# MCU.net
KiCad netlist of a schematic drawn in Altium Designer
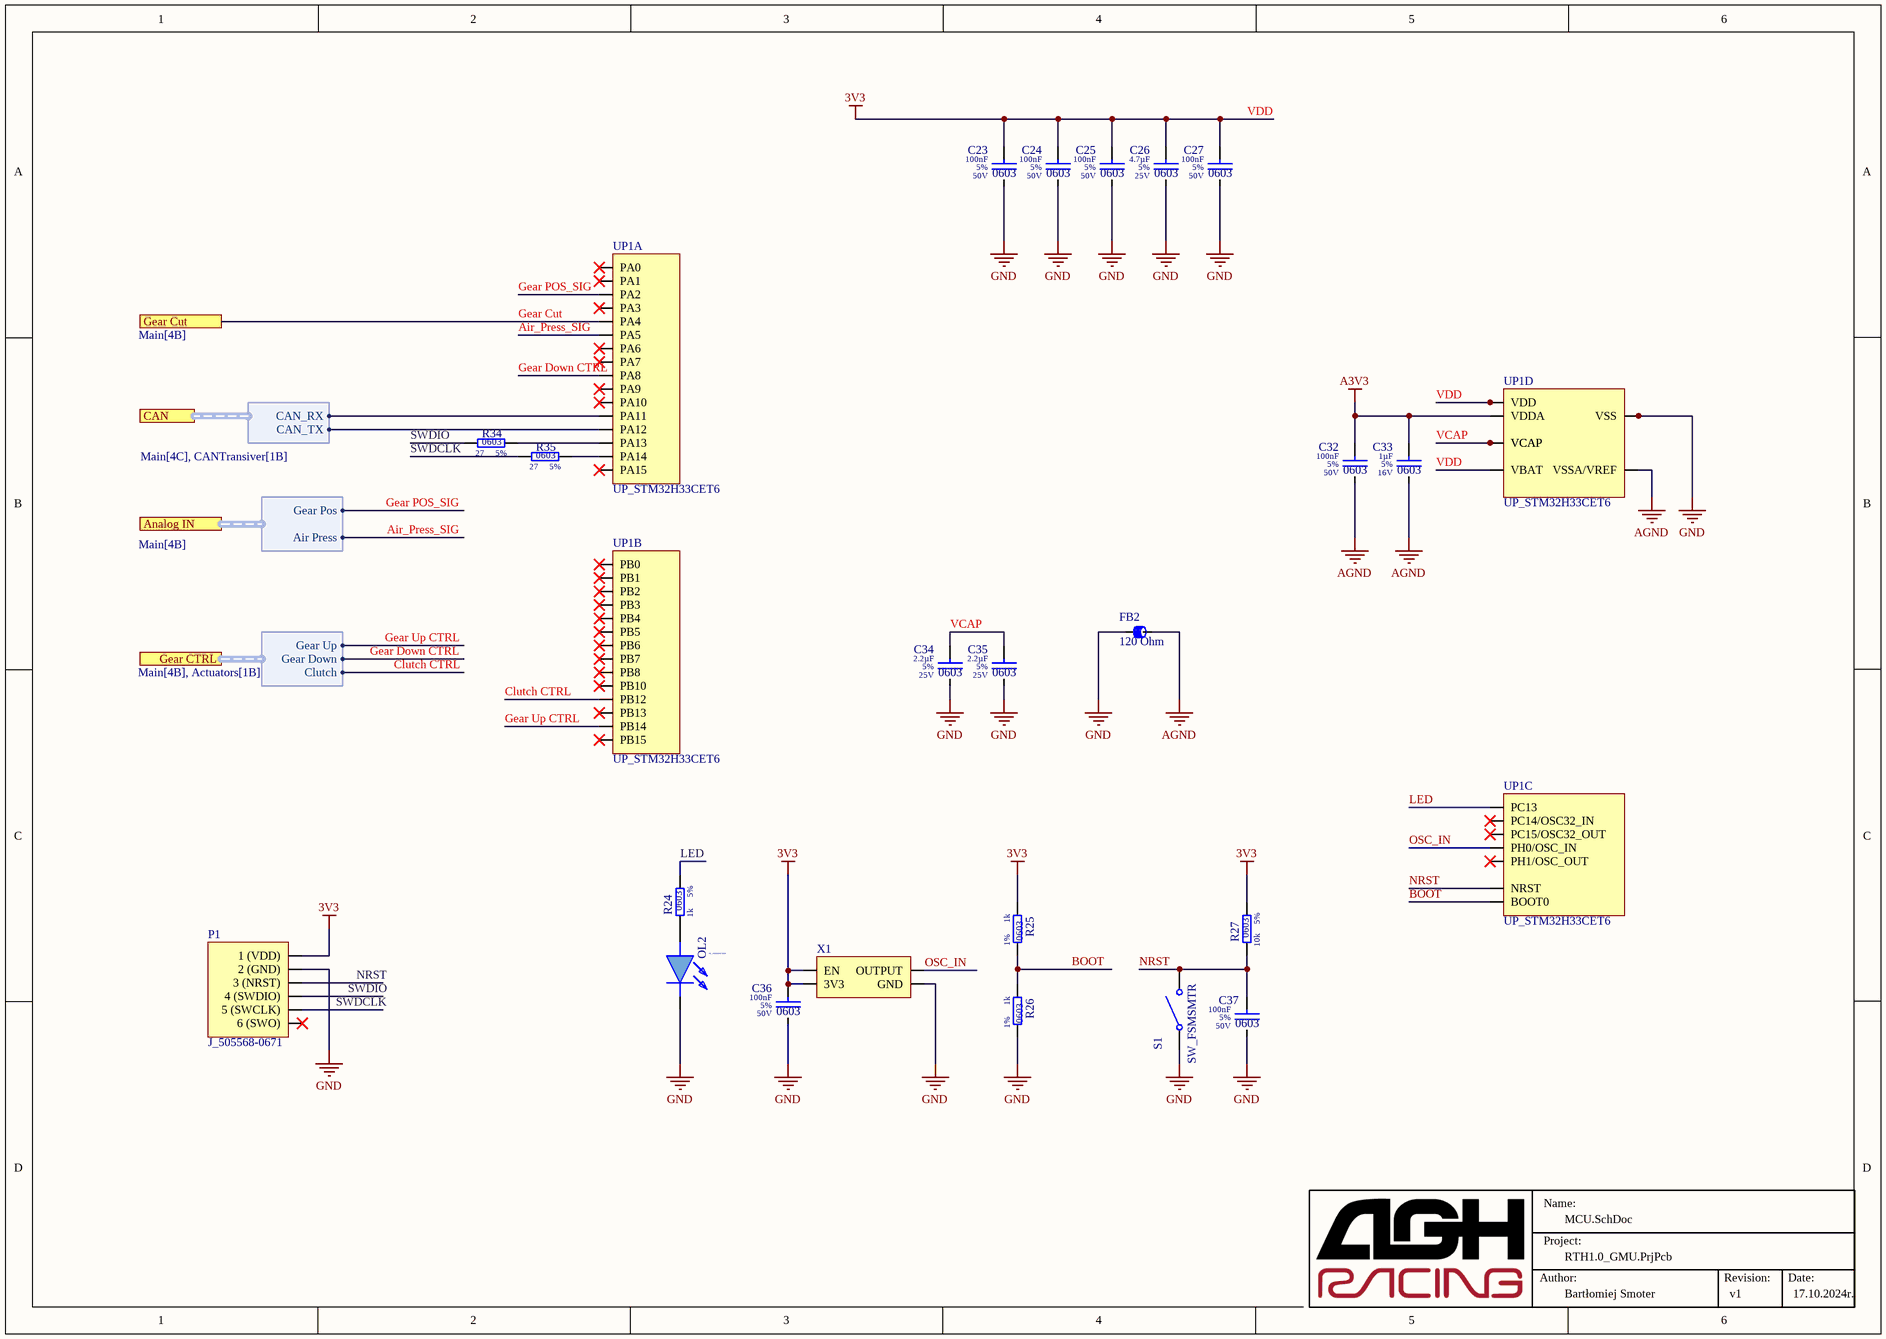
[diagram p0: MCU.SchDoc]

(export (version "E")
  (design (tool "Eeschema 10.0.6"))
  (components
    (comp (ref "C23")
      (value "100nF")
      (footprint "0603_HandSold_Capacitor")
      (description "C_100n_50V_0603_5")
      (fields
        (field (name "TOLERANCE") "5%")
        (field (name "VOLTAGE RATING") "50V")
        (field (name "CASE/PACKAGE") "0603")
      )
      (libsource (lib "Altium Concord Pro on A365") (part "Capacitor"))
    )
    (comp (ref "C24")
      (value "100nF")
      (footprint "0603_HandSold_Capacitor")
      (description "C_100n_50V_0603_5")
      (fields
        (field (name "TOLERANCE") "5%")
        (field (name "VOLTAGE RATING") "50V")
        (field (name "CASE/PACKAGE") "0603")
      )
      (libsource (lib "Altium Concord Pro on A365") (part "Capacitor"))
    )
    (comp (ref "C25")
      (value "100nF")
      (footprint "0603_HandSold_Capacitor")
      (description "C_100n_50V_0603_5")
      (fields
        (field (name "TOLERANCE") "5%")
        (field (name "VOLTAGE RATING") "50V")
        (field (name "CASE/PACKAGE") "0603")
      )
      (libsource (lib "Altium Concord Pro on A365") (part "Capacitor"))
    )
    (comp (ref "C26")
      (value "4.7µF")
      (footprint "0603_HandSold_Capacitor")
      (description "C_4.7u_25V_0603_5")
      (fields
        (field (name "TOLERANCE") "5%")
        (field (name "VOLTAGE RATING") "25V")
        (field (name "CASE/PACKAGE") "0603")
      )
      (libsource (lib "Altium Concord Pro on A365") (part "Capacitor"))
    )
    (comp (ref "C27")
      (value "100nF")
      (footprint "0603_HandSold_Capacitor")
      (description "C_100n_50V_0603_5")
      (fields
        (field (name "TOLERANCE") "5%")
        (field (name "VOLTAGE RATING") "50V")
        (field (name "CASE/PACKAGE") "0603")
      )
      (libsource (lib "Altium Concord Pro on A365") (part "Capacitor"))
    )
    (comp (ref "C32")
      (value "100nF")
      (footprint "0603_HandSold_Capacitor")
      (description "C_100n_50V_0603_5")
      (fields
        (field (name "TOLERANCE") "5%")
        (field (name "VOLTAGE RATING") "50V")
        (field (name "CASE/PACKAGE") "0603")
      )
      (libsource (lib "Altium Concord Pro on A365") (part "Capacitor"))
    )
    (comp (ref "C33")
      (value "1µF")
      (footprint "0603_HandSold_Capacitor")
      (description "C_1u_16V_0603_5")
      (fields
        (field (name "TOLERANCE") "5%")
        (field (name "VOLTAGE RATING") "16V")
        (field (name "CASE/PACKAGE") "0603")
      )
      (libsource (lib "Altium Concord Pro on A365") (part "Capacitor"))
    )
    (comp (ref "C34")
      (value "2.2µF")
      (footprint "0603_HandSold_Capacitor")
      (description "C_2.2u_25V_0603_5")
      (fields
        (field (name "TOLERANCE") "5%")
        (field (name "VOLTAGE RATING") "25V")
        (field (name "CASE/PACKAGE") "0603")
      )
      (libsource (lib "Altium Concord Pro on A365") (part "Capacitor"))
    )
    (comp (ref "C35")
      (value "2.2µF")
      (footprint "0603_HandSold_Capacitor")
      (description "C_2.2u_25V_0603_5")
      (fields
        (field (name "TOLERANCE") "5%")
        (field (name "VOLTAGE RATING") "25V")
        (field (name "CASE/PACKAGE") "0603")
      )
      (libsource (lib "Altium Concord Pro on A365") (part "Capacitor"))
    )
    (comp (ref "C36")
      (value "100nF")
      (footprint "0603_HandSold_Capacitor")
      (description "C_100n_50V_0603_5")
      (fields
        (field (name "TOLERANCE") "5%")
        (field (name "VOLTAGE RATING") "50V")
        (field (name "CASE/PACKAGE") "0603")
      )
      (libsource (lib "Altium Concord Pro on A365") (part "Capacitor"))
    )
    (comp (ref "C37")
      (value "100nF")
      (footprint "0603_HandSold_Capacitor")
      (description "C_100n_50V_0603_5")
      (fields
        (field (name "TOLERANCE") "5%")
        (field (name "VOLTAGE RATING") "50V")
        (field (name "CASE/PACKAGE") "0603")
      )
      (libsource (lib "Altium Concord Pro on A365") (part "Capacitor"))
    )
    (comp (ref "FB2")
      (value "FB_BLM21PG121SN1D")
      (footprint "0805_FB")
      (description "Ferrite Beads 120 OHM 25% Alternate Sizing Guide Below")
      (fields (field (name "IMPEDANCE") "120 Ohm"))
      (libsource (lib "Altium Concord Pro on A365") (part "FerriteBead"))
    )
    (comp (ref "OL2")
      (value "OL_150060BS75000")
      (footprint "0603_HandSold_LED")
      (description "LED 0603, Blue, 3.2V, 30mA, 105mW")
      (fields (field (name "POWER") "105mW"))
      (libsource (lib "Altium Concord Pro on A365") (part "OL_BLUE"))
    )
    (comp (ref "P1")
      (value "J_505568-0671")
      (footprint "505568-0671")
      (description "Male; Micro-Lock Plus; 6 Pos. 1.25mm; 1.5A 50V; Straight; SMT;")
      (libsource (lib "Altium Concord Pro on A365") (part "505568-0671"))
    )
    (comp (ref "R24")
      (value "R_1k_0603_5")
      (footprint "0603_HandSold_Resistor")
      (fields
        (field (name "TOLERANCE") "5%")
        (field (name "RESISTANCE") "1k")
        (field (name "CASE/PACKAGE") "0603")
        (field (name "POWER") "100mW")
      )
      (libsource (lib "Altium Concord Pro on A365") (part "Resistor"))
    )
    (comp (ref "R25")
      (value "R_1k_0603_1")
      (footprint "0603_HandSold_Resistor")
      (fields
        (field (name "TOLERANCE") "1%")
        (field (name "RESISTANCE") "1k")
        (field (name "CASE/PACKAGE") "0603")
        (field (name "POWER") "100mW")
      )
      (libsource (lib "Altium Concord Pro on A365") (part "Resistor"))
    )
    (comp (ref "R26")
      (value "R_1k_0603_1")
      (footprint "0603_HandSold_Resistor")
      (fields
        (field (name "TOLERANCE") "1%")
        (field (name "RESISTANCE") "1k")
        (field (name "CASE/PACKAGE") "0603")
        (field (name "POWER") "100mW")
      )
      (libsource (lib "Altium Concord Pro on A365") (part "Resistor"))
    )
    (comp (ref "R27")
      (value "R_10k_0603_5")
      (footprint "0603_HandSold_Resistor")
      (fields
        (field (name "TOLERANCE") "5%")
        (field (name "RESISTANCE") "10k")
        (field (name "CASE/PACKAGE") "0603")
        (field (name "POWER") "100mW")
      )
      (libsource (lib "Altium Concord Pro on A365") (part "Resistor"))
    )
    (comp (ref "R34")
      (value "R_27_0603_5")
      (footprint "0603_HandSold_Resistor")
      (fields
        (field (name "TOLERANCE") "5%")
        (field (name "RESISTANCE") "27")
        (field (name "CASE/PACKAGE") "0603")
        (field (name "POWER") "100mW")
      )
      (libsource (lib "Altium Concord Pro on A365") (part "Resistor"))
    )
    (comp (ref "R35")
      (value "R_27_0603_5")
      (footprint "0603_HandSold_Resistor")
      (fields
        (field (name "TOLERANCE") "5%")
        (field (name "RESISTANCE") "27")
        (field (name "CASE/PACKAGE") "0603")
        (field (name "POWER") "100mW")
      )
      (libsource (lib "Altium Concord Pro on A365") (part "Resistor"))
    )
    (comp (ref "S1")
      (value "SW_FSMSMTR")
      (footprint "TECO-FSMSMTR_V")
      (description "Switch; Tact; OFF-(ON); 50mA; 24V")
      (libsource (lib "Altium Concord Pro on A365") (part "Switch 2 Pin"))
    )
    (comp (ref "UP1")
      (value "UP_STM32H33CET6")
      (footprint "LQFP48")
      (description "MCU High-performance Arm Cortex-M33 MCU 512-Kbyte Flash 272-Kbyte RAM 250 MHz CPU")
      (libsource (lib "Altium Concord Pro on A365") (part "STM32F303xB / xC Series 48 Pins"))
    )
    (comp (ref "X1")
      (value "X_16MHz_LFSPXO066657CUTT")
      (footprint "X_2mm_2.5mm_oscillator")
      (libsource (lib "Altium Concord Pro on A365") (part "X_16MHz_LFSPXO066657CUTT"))
    )
  )
  (nets
    (net (code "4") (name "/Air_Press_SIG") (class "Default")
      (node (ref "UP1") (pin "15") (pinfunction "PA5_15") (pintype "passive"))
    )
    (net (code "5") (name "/BOOT") (class "Default")
      (node (ref "R25") (pin "2") (pinfunction "2_2") (pintype "passive"))
      (node (ref "R26") (pin "1") (pinfunction "1_1") (pintype "passive"))
      (node (ref "UP1") (pin "44") (pinfunction "BOOT0_44") (pintype "passive"))
    )
    (net (code "6") (name "/CAN_RX") (class "Default")
      (node (ref "UP1") (pin "32") (pinfunction "PA11_32") (pintype "passive"))
    )
    (net (code "7") (name "/CAN_TX") (class "Default")
      (node (ref "UP1") (pin "33") (pinfunction "PA12_33") (pintype "passive"))
    )
    (net (code "8") (name "/Clutch CTRL") (class "Default")
      (node (ref "UP1") (pin "25") (pinfunction "PB12_25") (pintype "passive"))
    )
    (net (code "9") (name "/Gear Cut") (class "Default")
      (node (ref "UP1") (pin "14") (pinfunction "PA4_14") (pintype "passive"))
    )
    (net (code "10") (name "/Gear Down CTRL") (class "Default")
      (node (ref "UP1") (pin "29") (pinfunction "PA8_29") (pintype "passive"))
    )
    (net (code "11") (name "/Gear POS_SIG") (class "Default")
      (node (ref "UP1") (pin "12") (pinfunction "PA2_12") (pintype "passive"))
    )
    (net (code "12") (name "/Gear Up CTRL") (class "Default")
      (node (ref "UP1") (pin "27") (pinfunction "PB14_27") (pintype "passive"))
    )
    (net (code "13") (name "/LED") (class "Default")
      (node (ref "R24") (pin "2") (pinfunction "2_2") (pintype "passive"))
      (node (ref "UP1") (pin "2") (pinfunction "PC13_2") (pintype "passive"))
    )
    (net (code "14") (name "/NRST") (class "Default")
      (node (ref "C37") (pin "1") (pinfunction "1_1") (pintype "passive"))
      (node (ref "P1") (pin "3") (pinfunction "3_(NRST)_3") (pintype "passive"))
      (node (ref "R27") (pin "1") (pinfunction "1_1") (pintype "passive"))
      (node (ref "S1") (pin "2") (pinfunction "2_2") (pintype "passive"))
      (node (ref "UP1") (pin "7") (pinfunction "NRST_7") (pintype "passive"))
    )
    (net (code "15") (name "/OSC_IN") (class "Default")
      (node (ref "UP1") (pin "5") (pinfunction "PH0/OSC_IN_5") (pintype "passive"))
      (node (ref "X1") (pin "3") (pinfunction "OUTPUT_3") (pintype "passive"))
    )
    (net (code "16") (name "/SWDCLK") (class "Default")
      (node (ref "P1") (pin "5") (pinfunction "5_(SWCLK)_5") (pintype "passive"))
      (node (ref "R35") (pin "1") (pinfunction "1_1") (pintype "passive"))
    )
    (net (code "17") (name "/SWDIO") (class "Default")
      (node (ref "P1") (pin "4") (pinfunction "4_(SWDIO)_4") (pintype "passive"))
      (node (ref "R34") (pin "1") (pinfunction "1_1") (pintype "passive"))
    )
    (net (code "18") (name "/VCAP") (class "Default")
      (node (ref "C34") (pin "1") (pinfunction "1_1") (pintype "passive"))
      (node (ref "C35") (pin "1") (pinfunction "1_1") (pintype "passive"))
      (node (ref "UP1") (pin "22") (pinfunction "VCAP_22") (pintype "power_in"))
      (node (ref "UP1") (pin "46") (pinfunction "VCAP_46") (pintype "power_in"))
    )
    (net (code "22") (name "3V3") (class "Default")
      (node (ref "C23") (pin "1") (pinfunction "1_1") (pintype "passive"))
      (node (ref "C24") (pin "1") (pinfunction "1_1") (pintype "passive"))
      (node (ref "C25") (pin "1") (pinfunction "1_1") (pintype "passive"))
      (node (ref "C26") (pin "1") (pinfunction "1_1") (pintype "passive"))
      (node (ref "C27") (pin "1") (pinfunction "1_1") (pintype "passive"))
      (node (ref "C36") (pin "1") (pinfunction "1_1") (pintype "passive"))
      (node (ref "P1") (pin "1") (pinfunction "1_(VDD)_1") (pintype "passive"))
      (node (ref "R25") (pin "1") (pinfunction "1_1") (pintype "passive"))
      (node (ref "R27") (pin "2") (pinfunction "2_2") (pintype "passive"))
      (node (ref "UP1") (pin "1") (pinfunction "VBAT_1") (pintype "passive"))
      (node (ref "UP1") (pin "24") (pinfunction "VDD_24") (pintype "passive"))
      (node (ref "UP1") (pin "36") (pinfunction "VDD_36") (pintype "passive"))
      (node (ref "UP1") (pin "48") (pinfunction "VDD_48") (pintype "passive"))
      (node (ref "X1") (pin "1") (pinfunction "EN_1") (pintype "passive"))
      (node (ref "X1") (pin "4") (pinfunction "3V3_4") (pintype "passive"))
    )
    (net (code "23") (name "A3V3") (class "Default")
      (node (ref "C32") (pin "1") (pinfunction "1_1") (pintype "passive"))
      (node (ref "C33") (pin "1") (pinfunction "1_1") (pintype "passive"))
      (node (ref "UP1") (pin "9") (pinfunction "VDDA_9") (pintype "passive"))
    )
    (net (code "24") (name "AGND") (class "Default")
      (node (ref "C32") (pin "2") (pinfunction "2_2") (pintype "passive"))
      (node (ref "C33") (pin "2") (pinfunction "2_2") (pintype "passive"))
      (node (ref "FB2") (pin "2") (pinfunction "2_2") (pintype "passive"))
      (node (ref "UP1") (pin "8") (pinfunction "VSSA/VREF_8") (pintype "passive"))
    )
    (net (code "25") (name "GND") (class "Default")
      (node (ref "C23") (pin "2") (pinfunction "2_2") (pintype "passive"))
      (node (ref "C24") (pin "2") (pinfunction "2_2") (pintype "passive"))
      (node (ref "C25") (pin "2") (pinfunction "2_2") (pintype "passive"))
      (node (ref "C26") (pin "2") (pinfunction "2_2") (pintype "passive"))
      (node (ref "C27") (pin "2") (pinfunction "2_2") (pintype "passive"))
      (node (ref "C34") (pin "2") (pinfunction "2_2") (pintype "passive"))
      (node (ref "C35") (pin "2") (pinfunction "2_2") (pintype "passive"))
      (node (ref "C36") (pin "2") (pinfunction "2_2") (pintype "passive"))
      (node (ref "C37") (pin "2") (pinfunction "2_2") (pintype "passive"))
      (node (ref "FB2") (pin "1") (pinfunction "1_1") (pintype "passive"))
      (node (ref "OL2") (pin "1") (pinfunction "K_1") (pintype "passive"))
      (node (ref "P1") (pin "2") (pinfunction "2_(GND)_2") (pintype "passive"))
      (node (ref "R26") (pin "2") (pinfunction "2_2") (pintype "passive"))
      (node (ref "S1") (pin "1") (pinfunction "1_1") (pintype "passive"))
      (node (ref "UP1") (pin "23") (pinfunction "VSS_23") (pintype "passive"))
      (node (ref "UP1") (pin "35") (pinfunction "VSS_35") (pintype "passive"))
      (node (ref "UP1") (pin "47") (pinfunction "VSS_47") (pintype "passive"))
      (node (ref "X1") (pin "2") (pinfunction "GND_2") (pintype "passive"))
    )
    (net (code "26") (name "Net-(OL2-A)") (class "Default")
      (node (ref "OL2") (pin "2") (pinfunction "A_2") (pintype "passive"))
      (node (ref "R24") (pin "1") (pinfunction "1_1") (pintype "passive"))
    )
    (net (code "27") (name "Net-(UP1A-PA13)") (class "Default")
      (node (ref "R34") (pin "2") (pinfunction "2_2") (pintype "passive"))
      (node (ref "UP1") (pin "34") (pinfunction "PA13_34") (pintype "passive"))
    )
    (net (code "28") (name "Net-(UP1A-PA14)") (class "Default")
      (node (ref "R35") (pin "2") (pinfunction "2_2") (pintype "passive"))
      (node (ref "UP1") (pin "37") (pinfunction "PA14_37") (pintype "passive"))
    )
    (net (code "29") (name "unconnected-(P1-6_(SWO)-Pad6)") (class "Default")
      (node (ref "P1") (pin "6") (pinfunction "6_(SWO)_6") (pintype "passive+no_connect"))
    )
    (net (code "30") (name "unconnected-(UP1A-PA0-Pad10)") (class "Default")
      (node (ref "UP1") (pin "10") (pinfunction "PA0_10") (pintype "passive+no_connect"))
    )
    (net (code "31") (name "unconnected-(UP1A-PA1-Pad11)") (class "Default")
      (node (ref "UP1") (pin "11") (pinfunction "PA1_11") (pintype "passive+no_connect"))
    )
    (net (code "32") (name "unconnected-(UP1A-PA3-Pad13)") (class "Default")
      (node (ref "UP1") (pin "13") (pinfunction "PA3_13") (pintype "passive+no_connect"))
    )
    (net (code "33") (name "unconnected-(UP1A-PA6-Pad16)") (class "Default")
      (node (ref "UP1") (pin "16") (pinfunction "PA6_16") (pintype "passive+no_connect"))
    )
    (net (code "34") (name "unconnected-(UP1A-PA7-Pad17)") (class "Default")
      (node (ref "UP1") (pin "17") (pinfunction "PA7_17") (pintype "passive+no_connect"))
    )
    (net (code "35") (name "unconnected-(UP1A-PA9-Pad30)") (class "Default")
      (node (ref "UP1") (pin "30") (pinfunction "PA9_30") (pintype "passive+no_connect"))
    )
    (net (code "36") (name "unconnected-(UP1A-PA10-Pad31)") (class "Default")
      (node (ref "UP1") (pin "31") (pinfunction "PA10_31") (pintype "passive+no_connect"))
    )
    (net (code "37") (name "unconnected-(UP1A-PA15-Pad38)") (class "Default")
      (node (ref "UP1") (pin "38") (pinfunction "PA15_38") (pintype "passive+no_connect"))
    )
    (net (code "38") (name "unconnected-(UP1B-PB0-Pad18)") (class "Default")
      (node (ref "UP1") (pin "18") (pinfunction "PB0_18") (pintype "passive+no_connect"))
    )
    (net (code "39") (name "unconnected-(UP1B-PB1-Pad19)") (class "Default")
      (node (ref "UP1") (pin "19") (pinfunction "PB1_19") (pintype "passive+no_connect"))
    )
    (net (code "40") (name "unconnected-(UP1B-PB2-Pad20)") (class "Default")
      (node (ref "UP1") (pin "20") (pinfunction "PB2_20") (pintype "passive+no_connect"))
    )
    (net (code "41") (name "unconnected-(UP1B-PB3-Pad39)") (class "Default")
      (node (ref "UP1") (pin "39") (pinfunction "PB3_39") (pintype "passive+no_connect"))
    )
    (net (code "42") (name "unconnected-(UP1B-PB4-Pad40)") (class "Default")
      (node (ref "UP1") (pin "40") (pinfunction "PB4_40") (pintype "passive+no_connect"))
    )
    (net (code "43") (name "unconnected-(UP1B-PB5-Pad41)") (class "Default")
      (node (ref "UP1") (pin "41") (pinfunction "PB5_41") (pintype "passive+no_connect"))
    )
    (net (code "44") (name "unconnected-(UP1B-PB6-Pad42)") (class "Default")
      (node (ref "UP1") (pin "42") (pinfunction "PB6_42") (pintype "passive+no_connect"))
    )
    (net (code "45") (name "unconnected-(UP1B-PB7-Pad43)") (class "Default")
      (node (ref "UP1") (pin "43") (pinfunction "PB7_43") (pintype "passive+no_connect"))
    )
    (net (code "46") (name "unconnected-(UP1B-PB8-Pad45)") (class "Default")
      (node (ref "UP1") (pin "45") (pinfunction "PB8_45") (pintype "passive+no_connect"))
    )
    (net (code "47") (name "unconnected-(UP1B-PB10-Pad21)") (class "Default")
      (node (ref "UP1") (pin "21") (pinfunction "PB10_21") (pintype "passive+no_connect"))
    )
    (net (code "48") (name "unconnected-(UP1B-PB13-Pad26)") (class "Default")
      (node (ref "UP1") (pin "26") (pinfunction "PB13_26") (pintype "passive+no_connect"))
    )
    (net (code "49") (name "unconnected-(UP1B-PB15-Pad28)") (class "Default")
      (node (ref "UP1") (pin "28") (pinfunction "PB15_28") (pintype "passive+no_connect"))
    )
    (net (code "50") (name "unconnected-(UP1C-PC14{slash}OSC32_IN-Pad3)") (class "Default")
      (node (ref "UP1") (pin "3") (pinfunction "PC14/OSC32_IN_3") (pintype "passive+no_connect"))
    )
    (net (code "51") (name "unconnected-(UP1C-PC15{slash}OSC32_OUT-Pad4)") (class "Default")
      (node (ref "UP1") (pin "4") (pinfunction "PC15/OSC32_OUT_4") (pintype "passive+no_connect"))
    )
    (net (code "52") (name "unconnected-(UP1C-PH1{slash}OSC_OUT-Pad6)") (class "Default")
      (node (ref "UP1") (pin "6") (pinfunction "PH1/OSC_OUT_6") (pintype "passive+no_connect"))
    )
  )
)
